# Device_Measurement_V1_3.net
KiCad netlist of a schematic drawn in EAGLE
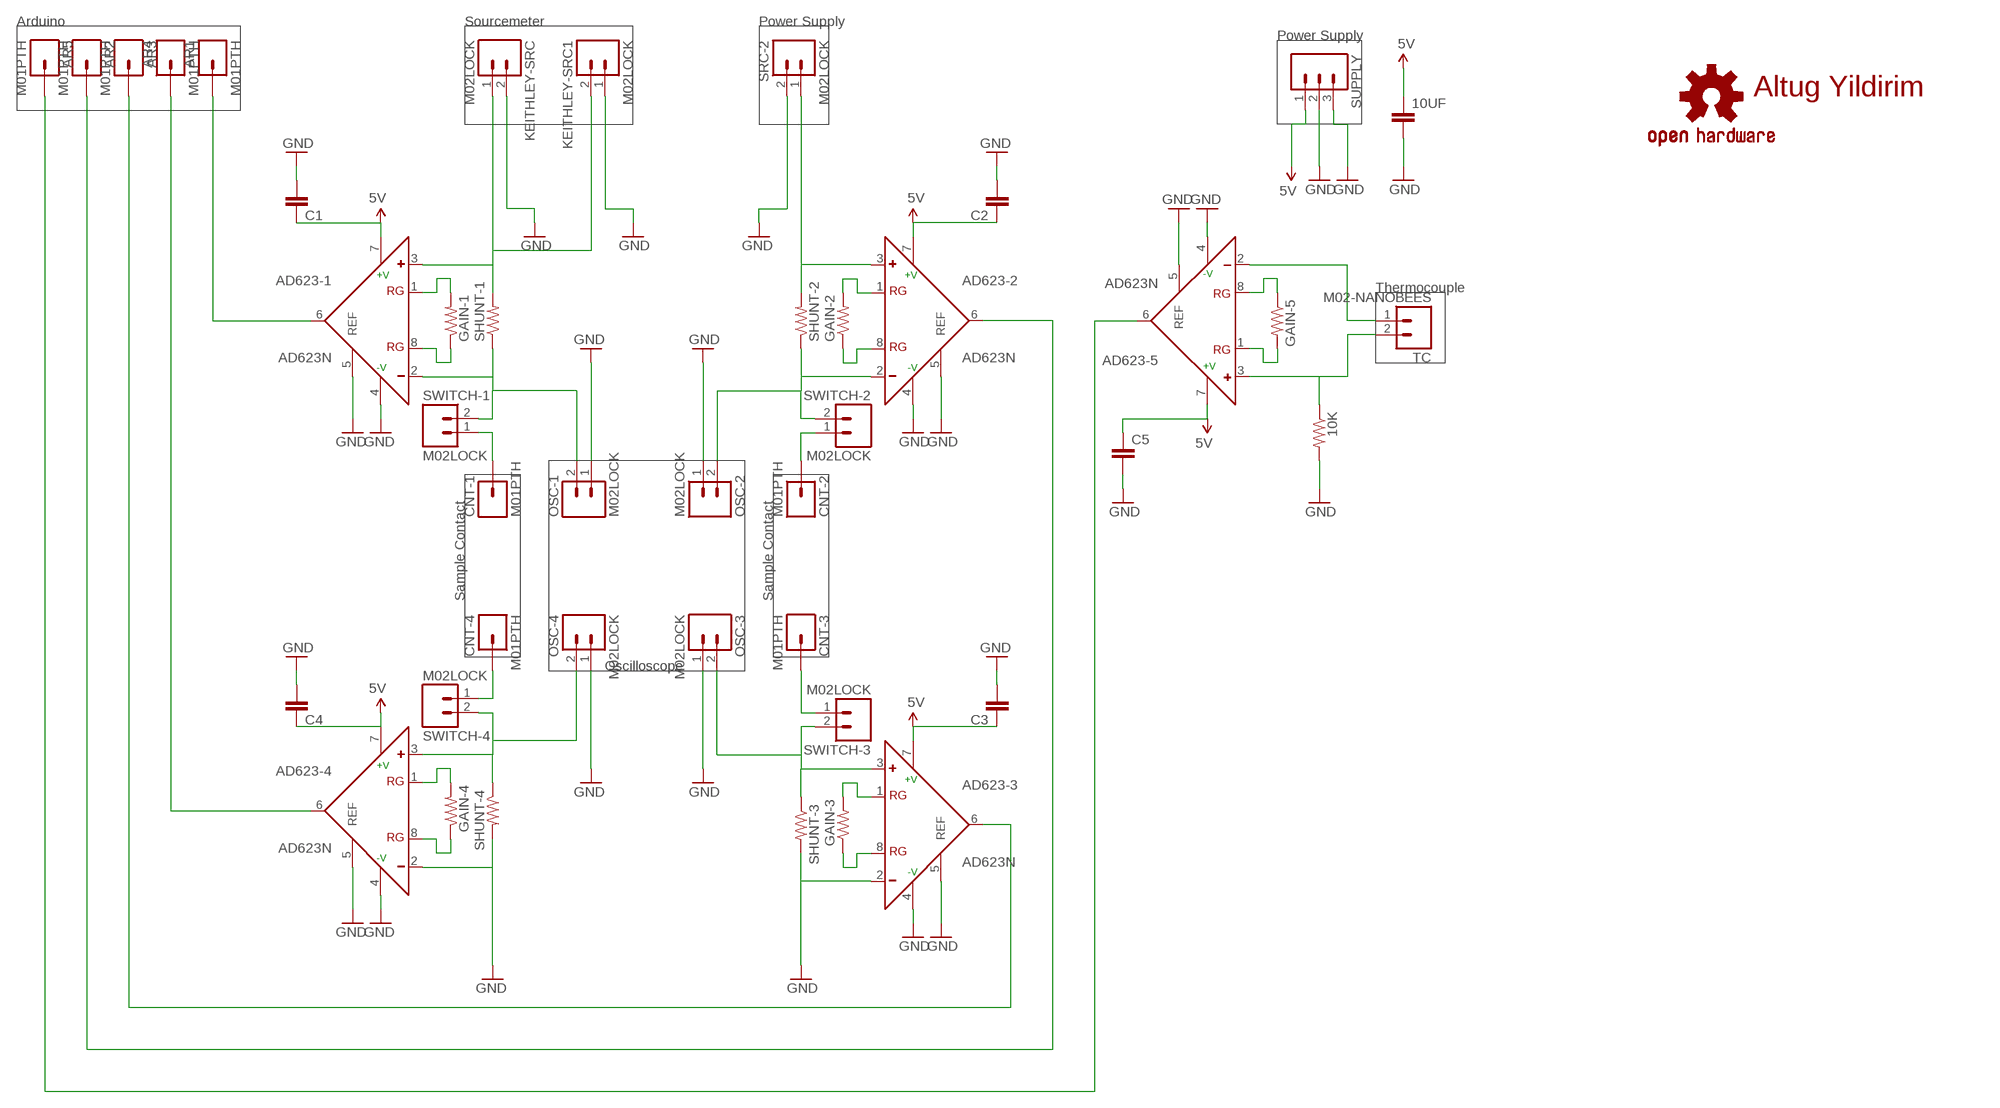
[diagram p0: schematic, sheet 1]

(export (version "E")
  (design (tool "Eeschema 10.0.6"))
  (components
    (comp (ref "10K")
      (value "R-US_0207/10")
      (footprint "eagle-import:0207_10")
      (libsource (lib "eagle-import") (part "R-US_0207/10"))
    )
    (comp (ref "10UF")
      (value "CAPPTH1")
      (footprint "eagle-import:CAP-PTH-5MM")
      (libsource (lib "eagle-import") (part "CAPPTH1"))
    )
    (comp (ref "AD623-1")
      (value "AD623N")
      (footprint "eagle-import:DIL08")
      (fields (field (name "MF") "ALTERA CORPORATION") (field (name "MPN") "AD623ANZ"))
      (libsource (lib "eagle-import") (part "AD623N"))
    )
    (comp (ref "AD623-2")
      (value "AD623N")
      (footprint "eagle-import:DIL08")
      (fields (field (name "MF") "ALTERA CORPORATION") (field (name "MPN") "AD623ANZ"))
      (libsource (lib "eagle-import") (part "AD623N"))
    )
    (comp (ref "AD623-3")
      (value "AD623N")
      (footprint "eagle-import:DIL08")
      (fields (field (name "MF") "ALTERA CORPORATION") (field (name "MPN") "AD623ANZ"))
      (libsource (lib "eagle-import") (part "AD623N"))
    )
    (comp (ref "AD623-4")
      (value "AD623N")
      (footprint "eagle-import:DIL08")
      (fields (field (name "MF") "ALTERA CORPORATION") (field (name "MPN") "AD623ANZ"))
      (libsource (lib "eagle-import") (part "AD623N"))
    )
    (comp (ref "AD623-5")
      (value "AD623N")
      (footprint "eagle-import:DIL08")
      (fields (field (name "MF") "ALTERA CORPORATION") (field (name "MPN") "AD623ANZ"))
      (libsource (lib "eagle-import") (part "AD623N"))
    )
    (comp (ref "AR1")
      (value "M01PTH")
      (footprint "eagle-import:1X01")
      (libsource (lib "eagle-import") (part "M01PTH"))
    )
    (comp (ref "AR2")
      (value "M01PTH")
      (footprint "eagle-import:1X01")
      (libsource (lib "eagle-import") (part "M01PTH"))
    )
    (comp (ref "AR3")
      (value "M01PTH")
      (footprint "eagle-import:1X01")
      (libsource (lib "eagle-import") (part "M01PTH"))
    )
    (comp (ref "AR4")
      (value "M01PTH")
      (footprint "eagle-import:1X01")
      (libsource (lib "eagle-import") (part "M01PTH"))
    )
    (comp (ref "AR5")
      (value "M01PTH")
      (footprint "eagle-import:1X01")
      (libsource (lib "eagle-import") (part "M01PTH"))
    )
    (comp (ref "C1")
      (value "CAPPTH1")
      (footprint "eagle-import:CAP-PTH-5MM")
      (libsource (lib "eagle-import") (part "CAPPTH1"))
    )
    (comp (ref "C2")
      (value "CAPPTH1")
      (footprint "eagle-import:CAP-PTH-5MM")
      (libsource (lib "eagle-import") (part "CAPPTH1"))
    )
    (comp (ref "C3")
      (value "CAPPTH1")
      (footprint "eagle-import:CAP-PTH-5MM")
      (libsource (lib "eagle-import") (part "CAPPTH1"))
    )
    (comp (ref "C4")
      (value "CAPPTH1")
      (footprint "eagle-import:CAP-PTH-5MM")
      (libsource (lib "eagle-import") (part "CAPPTH1"))
    )
    (comp (ref "C5")
      (value "CAPPTH1")
      (footprint "eagle-import:CAP-PTH-5MM")
      (libsource (lib "eagle-import") (part "CAPPTH1"))
    )
    (comp (ref "CNT-1")
      (value "M01PTH")
      (footprint "eagle-import:1X01")
      (libsource (lib "eagle-import") (part "M01PTH"))
    )
    (comp (ref "CNT-2")
      (value "M01PTH")
      (footprint "eagle-import:1X01")
      (libsource (lib "eagle-import") (part "M01PTH"))
    )
    (comp (ref "CNT-3")
      (value "M01PTH")
      (footprint "eagle-import:1X01")
      (libsource (lib "eagle-import") (part "M01PTH"))
    )
    (comp (ref "CNT-4")
      (value "M01PTH")
      (footprint "eagle-import:1X01")
      (libsource (lib "eagle-import") (part "M01PTH"))
    )
    (comp (ref "GAIN-1")
      (value "R-US_0207/10")
      (footprint "eagle-import:0207_10")
      (libsource (lib "eagle-import") (part "R-US_0207/10"))
    )
    (comp (ref "GAIN-2")
      (value "R-US_0207/10")
      (footprint "eagle-import:0207_10")
      (libsource (lib "eagle-import") (part "R-US_0207/10"))
    )
    (comp (ref "GAIN-3")
      (value "R-US_0207/10")
      (footprint "eagle-import:0207_10")
      (libsource (lib "eagle-import") (part "R-US_0207/10"))
    )
    (comp (ref "GAIN-4")
      (value "R-US_0207/10")
      (footprint "eagle-import:0207_10")
      (libsource (lib "eagle-import") (part "R-US_0207/10"))
    )
    (comp (ref "GAIN-5")
      (value "R-US_0207/10")
      (footprint "eagle-import:0207_10")
      (libsource (lib "eagle-import") (part "R-US_0207/10"))
    )
    (comp (ref "KEITHLEY-SRC")
      (value "M02LOCK")
      (footprint "eagle-import:1X02_LOCK")
      (libsource (lib "eagle-import") (part "M02LOCK"))
    )
    (comp (ref "KEITHLEY-SRC1")
      (value "M02LOCK")
      (footprint "eagle-import:1X02_LOCK")
      (libsource (lib "eagle-import") (part "M02LOCK"))
    )
    (comp (ref "LOGO1")
      (value "OSHW-LOGOM")
      (footprint "eagle-import:OSHW-LOGO-M")
      (libsource (lib "eagle-import") (part "OSHW-LOGOM"))
    )
    (comp (ref "OSC-1")
      (value "M02LOCK")
      (footprint "eagle-import:1X02_LOCK")
      (libsource (lib "eagle-import") (part "M02LOCK"))
    )
    (comp (ref "OSC-2")
      (value "M02LOCK")
      (footprint "eagle-import:1X02_LOCK")
      (libsource (lib "eagle-import") (part "M02LOCK"))
    )
    (comp (ref "OSC-3")
      (value "M02LOCK")
      (footprint "eagle-import:1X02_LOCK")
      (libsource (lib "eagle-import") (part "M02LOCK"))
    )
    (comp (ref "OSC-4")
      (value "M02LOCK")
      (footprint "eagle-import:1X02_LOCK")
      (libsource (lib "eagle-import") (part "M02LOCK"))
    )
    (comp (ref "SHUNT-1")
      (value "RESISTOR1206")
      (footprint "eagle-import:1206")
      (libsource (lib "eagle-import") (part "RESISTOR1206"))
    )
    (comp (ref "SHUNT-2")
      (value "RESISTOR1206")
      (footprint "eagle-import:1206")
      (libsource (lib "eagle-import") (part "RESISTOR1206"))
    )
    (comp (ref "SHUNT-3")
      (value "RESISTOR1206")
      (footprint "eagle-import:1206")
      (libsource (lib "eagle-import") (part "RESISTOR1206"))
    )
    (comp (ref "SHUNT-4")
      (value "RESISTOR1206")
      (footprint "eagle-import:1206")
      (libsource (lib "eagle-import") (part "RESISTOR1206"))
    )
    (comp (ref "SRC-2")
      (value "M02LOCK")
      (footprint "eagle-import:1X02_LOCK")
      (libsource (lib "eagle-import") (part "M02LOCK"))
    )
    (comp (ref "SUPPLY")
      (value "M03PTH")
      (footprint "eagle-import:1X03")
      (libsource (lib "eagle-import") (part "M03PTH"))
    )
    (comp (ref "SWITCH-1")
      (value "M02LOCK")
      (footprint "eagle-import:1X02_LOCK")
      (libsource (lib "eagle-import") (part "M02LOCK"))
    )
    (comp (ref "SWITCH-2")
      (value "M02LOCK")
      (footprint "eagle-import:1X02_LOCK")
      (libsource (lib "eagle-import") (part "M02LOCK"))
    )
    (comp (ref "SWITCH-3")
      (value "M02LOCK")
      (footprint "eagle-import:1X02_LOCK")
      (libsource (lib "eagle-import") (part "M02LOCK"))
    )
    (comp (ref "SWITCH-4")
      (value "M02LOCK")
      (footprint "eagle-import:1X02_LOCK")
      (libsource (lib "eagle-import") (part "M02LOCK"))
    )
    (comp (ref "TC")
      (value "M02-NANOBEES")
      (footprint "eagle-import:M02-NANOBEES")
      (libsource (lib "eagle-import") (part "M02-NANOBEES"))
    )
  )
  (nets
    (net (code "1") (name "5V") (class "Default")
      (node (ref "10UF") (pin "1") (pinfunction "1_1") (pintype "passive"))
      (node (ref "AD623-1") (pin "7") (pinfunction "+V_7") (pintype "power_in"))
      (node (ref "AD623-2") (pin "7") (pinfunction "+V_7") (pintype "power_in"))
      (node (ref "AD623-3") (pin "7") (pinfunction "+V_7") (pintype "power_in"))
      (node (ref "AD623-4") (pin "7") (pinfunction "+V_7") (pintype "power_in"))
      (node (ref "AD623-5") (pin "7") (pinfunction "+V_7") (pintype "power_in"))
      (node (ref "C1") (pin "1") (pinfunction "1_1") (pintype "passive"))
      (node (ref "C2") (pin "1") (pinfunction "1_1") (pintype "passive"))
      (node (ref "C3") (pin "1") (pinfunction "1_1") (pintype "passive"))
      (node (ref "C4") (pin "1") (pinfunction "1_1") (pintype "passive"))
      (node (ref "C5") (pin "1") (pinfunction "1_1") (pintype "passive"))
      (node (ref "SUPPLY") (pin "1") (pinfunction "1_1") (pintype "passive"))
    )
    (net (code "2") (name "GND") (class "Default")
      (node (ref "10K") (pin "2") (pinfunction "2_2") (pintype "passive"))
      (node (ref "10UF") (pin "2") (pinfunction "2_2") (pintype "passive"))
      (node (ref "AD623-1") (pin "4") (pinfunction "-V_4") (pintype "power_in"))
      (node (ref "AD623-1") (pin "5") (pinfunction "REF_5") (pintype "passive"))
      (node (ref "AD623-2") (pin "4") (pinfunction "-V_4") (pintype "power_in"))
      (node (ref "AD623-2") (pin "5") (pinfunction "REF_5") (pintype "passive"))
      (node (ref "AD623-3") (pin "2") (pinfunction "-_2") (pintype "input"))
      (node (ref "AD623-3") (pin "4") (pinfunction "-V_4") (pintype "power_in"))
      (node (ref "AD623-3") (pin "5") (pinfunction "REF_5") (pintype "passive"))
      (node (ref "AD623-4") (pin "2") (pinfunction "-_2") (pintype "input"))
      (node (ref "AD623-4") (pin "4") (pinfunction "-V_4") (pintype "power_in"))
      (node (ref "AD623-4") (pin "5") (pinfunction "REF_5") (pintype "passive"))
      (node (ref "AD623-5") (pin "4") (pinfunction "-V_4") (pintype "power_in"))
      (node (ref "AD623-5") (pin "5") (pinfunction "REF_5") (pintype "passive"))
      (node (ref "C1") (pin "2") (pinfunction "2_2") (pintype "passive"))
      (node (ref "C2") (pin "2") (pinfunction "2_2") (pintype "passive"))
      (node (ref "C3") (pin "2") (pinfunction "2_2") (pintype "passive"))
      (node (ref "C4") (pin "2") (pinfunction "2_2") (pintype "passive"))
      (node (ref "C5") (pin "2") (pinfunction "2_2") (pintype "passive"))
      (node (ref "KEITHLEY-SRC") (pin "2") (pinfunction "2_2") (pintype "passive"))
      (node (ref "KEITHLEY-SRC1") (pin "1") (pinfunction "1_1") (pintype "passive"))
      (node (ref "OSC-1") (pin "1") (pinfunction "1_1") (pintype "passive"))
      (node (ref "OSC-2") (pin "1") (pinfunction "1_1") (pintype "passive"))
      (node (ref "OSC-3") (pin "1") (pinfunction "1_1") (pintype "passive"))
      (node (ref "OSC-4") (pin "1") (pinfunction "1_1") (pintype "passive"))
      (node (ref "SHUNT-3") (pin "2") (pinfunction "2_2") (pintype "passive"))
      (node (ref "SHUNT-4") (pin "2") (pinfunction "2_2") (pintype "passive"))
      (node (ref "SRC-2") (pin "2") (pinfunction "2_2") (pintype "passive"))
      (node (ref "SUPPLY") (pin "2") (pinfunction "2_2") (pintype "passive"))
      (node (ref "SUPPLY") (pin "3") (pinfunction "3_3") (pintype "passive"))
    )
    (net (code "3") (name "Net-(AD623-1-+)") (class "Default")
      (node (ref "AD623-1") (pin "3") (pinfunction "+_3") (pintype "input"))
      (node (ref "KEITHLEY-SRC") (pin "1") (pinfunction "1_1") (pintype "passive"))
      (node (ref "KEITHLEY-SRC1") (pin "2") (pinfunction "2_2") (pintype "passive"))
      (node (ref "SHUNT-1") (pin "2") (pinfunction "2_2") (pintype "passive"))
    )
    (net (code "4") (name "Net-(AD623-1--)") (class "Default")
      (node (ref "AD623-1") (pin "2") (pinfunction "-_2") (pintype "input"))
      (node (ref "OSC-1") (pin "2") (pinfunction "2_2") (pintype "passive"))
      (node (ref "SHUNT-1") (pin "1") (pinfunction "1_1") (pintype "passive"))
      (node (ref "SWITCH-1") (pin "2") (pinfunction "2_2") (pintype "passive"))
    )
    (net (code "5") (name "Net-(AD623-1-OUT)") (class "Default")
      (node (ref "AD623-1") (pin "6") (pinfunction "OUT_6") (pintype "output"))
      (node (ref "AR1") (pin "1") (pinfunction "1_1") (pintype "passive"))
    )
    (net (code "6") (name "Net-(AD623-1-RG-Pad1)") (class "Default")
      (node (ref "AD623-1") (pin "1") (pinfunction "RG_1") (pintype "passive"))
      (node (ref "GAIN-1") (pin "2") (pinfunction "2_2") (pintype "passive"))
    )
    (net (code "7") (name "Net-(AD623-1-RG-Pad8)") (class "Default")
      (node (ref "AD623-1") (pin "8") (pinfunction "RG_8") (pintype "passive"))
      (node (ref "GAIN-1") (pin "1") (pinfunction "1_1") (pintype "passive"))
    )
    (net (code "8") (name "Net-(AD623-2-+)") (class "Default")
      (node (ref "AD623-2") (pin "3") (pinfunction "+_3") (pintype "input"))
      (node (ref "SHUNT-2") (pin "2") (pinfunction "2_2") (pintype "passive"))
      (node (ref "SRC-2") (pin "1") (pinfunction "1_1") (pintype "passive"))
    )
    (net (code "9") (name "Net-(AD623-2--)") (class "Default")
      (node (ref "AD623-2") (pin "2") (pinfunction "-_2") (pintype "input"))
      (node (ref "OSC-2") (pin "2") (pinfunction "2_2") (pintype "passive"))
      (node (ref "SHUNT-2") (pin "1") (pinfunction "1_1") (pintype "passive"))
      (node (ref "SWITCH-2") (pin "2") (pinfunction "2_2") (pintype "passive"))
    )
    (net (code "10") (name "Net-(AD623-2-OUT)") (class "Default")
      (node (ref "AD623-2") (pin "6") (pinfunction "OUT_6") (pintype "output"))
      (node (ref "AR2") (pin "1") (pinfunction "1_1") (pintype "passive"))
    )
    (net (code "11") (name "Net-(AD623-2-RG-Pad1)") (class "Default")
      (node (ref "AD623-2") (pin "1") (pinfunction "RG_1") (pintype "passive"))
      (node (ref "GAIN-2") (pin "2") (pinfunction "2_2") (pintype "passive"))
    )
    (net (code "12") (name "Net-(AD623-2-RG-Pad8)") (class "Default")
      (node (ref "AD623-2") (pin "8") (pinfunction "RG_8") (pintype "passive"))
      (node (ref "GAIN-2") (pin "1") (pinfunction "1_1") (pintype "passive"))
    )
    (net (code "13") (name "Net-(AD623-3-+)") (class "Default")
      (node (ref "AD623-3") (pin "3") (pinfunction "+_3") (pintype "input"))
      (node (ref "OSC-3") (pin "2") (pinfunction "2_2") (pintype "passive"))
      (node (ref "SHUNT-3") (pin "1") (pinfunction "1_1") (pintype "passive"))
      (node (ref "SWITCH-3") (pin "2") (pinfunction "2_2") (pintype "passive"))
    )
    (net (code "14") (name "Net-(AD623-3-OUT)") (class "Default")
      (node (ref "AD623-3") (pin "6") (pinfunction "OUT_6") (pintype "output"))
      (node (ref "AR3") (pin "1") (pinfunction "1_1") (pintype "passive"))
    )
    (net (code "15") (name "Net-(AD623-3-RG-Pad1)") (class "Default")
      (node (ref "AD623-3") (pin "1") (pinfunction "RG_1") (pintype "passive"))
      (node (ref "GAIN-3") (pin "2") (pinfunction "2_2") (pintype "passive"))
    )
    (net (code "16") (name "Net-(AD623-3-RG-Pad8)") (class "Default")
      (node (ref "AD623-3") (pin "8") (pinfunction "RG_8") (pintype "passive"))
      (node (ref "GAIN-3") (pin "1") (pinfunction "1_1") (pintype "passive"))
    )
    (net (code "17") (name "Net-(AD623-4-+)") (class "Default")
      (node (ref "AD623-4") (pin "3") (pinfunction "+_3") (pintype "input"))
      (node (ref "OSC-4") (pin "2") (pinfunction "2_2") (pintype "passive"))
      (node (ref "SHUNT-4") (pin "1") (pinfunction "1_1") (pintype "passive"))
      (node (ref "SWITCH-4") (pin "2") (pinfunction "2_2") (pintype "passive"))
    )
    (net (code "18") (name "Net-(AD623-4-OUT)") (class "Default")
      (node (ref "AD623-4") (pin "6") (pinfunction "OUT_6") (pintype "output"))
      (node (ref "AR4") (pin "1") (pinfunction "1_1") (pintype "passive"))
    )
    (net (code "19") (name "Net-(AD623-4-RG-Pad1)") (class "Default")
      (node (ref "AD623-4") (pin "1") (pinfunction "RG_1") (pintype "passive"))
      (node (ref "GAIN-4") (pin "2") (pinfunction "2_2") (pintype "passive"))
    )
    (net (code "20") (name "Net-(AD623-4-RG-Pad8)") (class "Default")
      (node (ref "AD623-4") (pin "8") (pinfunction "RG_8") (pintype "passive"))
      (node (ref "GAIN-4") (pin "1") (pinfunction "1_1") (pintype "passive"))
    )
    (net (code "21") (name "Net-(AD623-5-+)") (class "Default")
      (node (ref "10K") (pin "1") (pinfunction "1_1") (pintype "passive"))
      (node (ref "AD623-5") (pin "3") (pinfunction "+_3") (pintype "input"))
      (node (ref "TC") (pin "2") (pinfunction "2_2") (pintype "passive"))
    )
    (net (code "22") (name "Net-(AD623-5--)") (class "Default")
      (node (ref "AD623-5") (pin "2") (pinfunction "-_2") (pintype "input"))
      (node (ref "TC") (pin "1") (pinfunction "1_1") (pintype "passive"))
    )
    (net (code "23") (name "Net-(AD623-5-OUT)") (class "Default")
      (node (ref "AD623-5") (pin "6") (pinfunction "OUT_6") (pintype "output"))
      (node (ref "AR5") (pin "1") (pinfunction "1_1") (pintype "passive"))
    )
    (net (code "24") (name "Net-(AD623-5-RG-Pad1)") (class "Default")
      (node (ref "AD623-5") (pin "1") (pinfunction "RG_1") (pintype "passive"))
      (node (ref "GAIN-5") (pin "2") (pinfunction "2_2") (pintype "passive"))
    )
    (net (code "25") (name "Net-(AD623-5-RG-Pad8)") (class "Default")
      (node (ref "AD623-5") (pin "8") (pinfunction "RG_8") (pintype "passive"))
      (node (ref "GAIN-5") (pin "1") (pinfunction "1_1") (pintype "passive"))
    )
    (net (code "26") (name "Net-(CNT-1-Pad1)") (class "Default")
      (node (ref "CNT-1") (pin "1") (pinfunction "1_1") (pintype "passive"))
      (node (ref "SWITCH-1") (pin "1") (pinfunction "1_1") (pintype "passive"))
    )
    (net (code "27") (name "Net-(CNT-2-Pad1)") (class "Default")
      (node (ref "CNT-2") (pin "1") (pinfunction "1_1") (pintype "passive"))
      (node (ref "SWITCH-2") (pin "1") (pinfunction "1_1") (pintype "passive"))
    )
    (net (code "28") (name "Net-(CNT-3-Pad1)") (class "Default")
      (node (ref "CNT-3") (pin "1") (pinfunction "1_1") (pintype "passive"))
      (node (ref "SWITCH-3") (pin "1") (pinfunction "1_1") (pintype "passive"))
    )
    (net (code "29") (name "Net-(CNT-4-Pad1)") (class "Default")
      (node (ref "CNT-4") (pin "1") (pinfunction "1_1") (pintype "passive"))
      (node (ref "SWITCH-4") (pin "1") (pinfunction "1_1") (pintype "passive"))
    )
  )
)
